# Water_Sensor.net
KiCad netlist of a schematic drawn in EAGLE
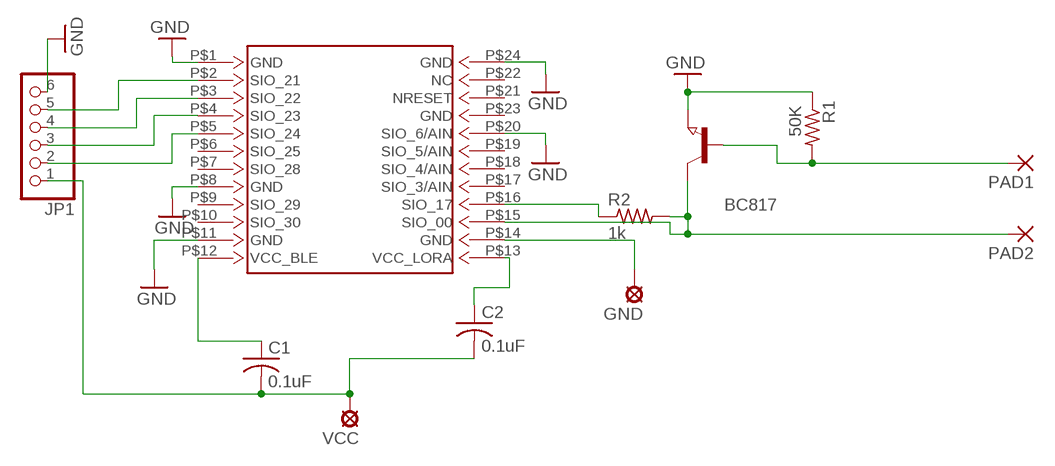
[diagram p0: schematic, sheet 1]

(export (version "E")
  (design (tool "Eeschema 10.0.6"))
  (components
    (comp (ref "BC817")
      (value "NPN-TRANSISTOR_SOT23")
      (footprint "eagle-import:SOT23")
      (libsource (lib "eagle-import") (part "NPN-TRANSISTOR_SOT23"))
    )
    (comp (ref "C1")
      (value "0.1uF")
      (footprint "eagle-import:C0805")
      (libsource (lib "eagle-import") (part "C-USC0805"))
    )
    (comp (ref "C2")
      (value "0.1uF")
      (footprint "eagle-import:C0805")
      (libsource (lib "eagle-import") (part "C-USC0805"))
    )
    (comp (ref "GND")
      (value "SE13")
      (footprint "eagle-import:SE13")
      (libsource (lib "eagle-import") (part "SE13"))
    )
    (comp (ref "JP1")
      (value "PINHD-1X6")
      (footprint "eagle-import:1X06")
      (libsource (lib "eagle-import") (part "PINHD-1X6"))
    )
    (comp (ref "PAD1")
      (value "SMD5")
      (footprint "eagle-import:SMD2,54-5,08")
      (libsource (lib "eagle-import") (part "SMD5"))
    )
    (comp (ref "PAD2")
      (value "SMD5")
      (footprint "eagle-import:SMD2,54-5,08")
      (libsource (lib "eagle-import") (part "SMD5"))
    )
    (comp (ref "R1")
      (value "50K")
      (footprint "eagle-import:M0805")
      (libsource (lib "eagle-import") (part "R-US_M0805"))
    )
    (comp (ref "R2")
      (value "1k")
      (footprint "eagle-import:M0805")
      (libsource (lib "eagle-import") (part "R-US_M0805"))
    )
    (comp (ref "RM191")
      (value "RM191RM1XX")
      (footprint "eagle-import:RM191")
      (libsource (lib "eagle-import") (part "RM191RM1XX"))
    )
    (comp (ref "VCC")
      (value "SE13")
      (footprint "eagle-import:SE13")
      (libsource (lib "eagle-import") (part "SE13"))
    )
  )
  (nets
    (net (code "1") (name "GND") (class "Default")
      (node (ref "BC817") (pin "2") (pinfunction "E_2") (pintype "passive"))
      (node (ref "GND") (pin "MP") (pinfunction "MP_MP") (pintype "passive"))
      (node (ref "JP1") (pin "6") (pinfunction "6_6") (pintype "passive"))
      (node (ref "R1") (pin "1") (pinfunction "1_1") (pintype "passive"))
      (node (ref "RM191") (pin "P$1") (pinfunction "GND_P$1") (pintype "bidirectional"))
      (node (ref "RM191") (pin "P$11") (pinfunction "GND_P$11") (pintype "bidirectional"))
      (node (ref "RM191") (pin "P$14") (pinfunction "GND_P$14") (pintype "bidirectional"))
      (node (ref "RM191") (pin "P$20") (pinfunction "SIO_6/AIN_P$20") (pintype "bidirectional"))
      (node (ref "RM191") (pin "P$24") (pinfunction "GND_P$24") (pintype "bidirectional"))
      (node (ref "RM191") (pin "P$8") (pinfunction "GND_P$8") (pintype "bidirectional"))
    )
    (net (code "2") (name "Net-(BC817-B)") (class "Default")
      (node (ref "BC817") (pin "1") (pinfunction "B_1") (pintype "passive"))
      (node (ref "PAD1") (pin "1") (pinfunction "P_1") (pintype "passive"))
      (node (ref "R1") (pin "2") (pinfunction "2_2") (pintype "passive"))
    )
    (net (code "3") (name "Net-(BC817-C)") (class "Default")
      (node (ref "BC817") (pin "3") (pinfunction "C_3") (pintype "passive"))
      (node (ref "PAD2") (pin "1") (pinfunction "P_1") (pintype "passive"))
      (node (ref "R2") (pin "2") (pinfunction "2_2") (pintype "passive"))
      (node (ref "RM191") (pin "P$15") (pinfunction "SIO_00_P$15") (pintype "bidirectional"))
    )
    (net (code "4") (name "Net-(C1-Pad2)") (class "Default")
      (node (ref "C1") (pin "2") (pinfunction "2_2") (pintype "passive"))
      (node (ref "C2") (pin "2") (pinfunction "2_2") (pintype "passive"))
      (node (ref "JP1") (pin "1") (pinfunction "1_1") (pintype "passive"))
      (node (ref "VCC") (pin "MP") (pinfunction "MP_MP") (pintype "passive"))
    )
    (net (code "5") (name "Net-(RM191-SIO_17)") (class "Default")
      (node (ref "R2") (pin "1") (pinfunction "1_1") (pintype "passive"))
      (node (ref "RM191") (pin "P$16") (pinfunction "SIO_17_P$16") (pintype "bidirectional"))
    )
    (net (code "6") (name "Net-(RM191-SIO_21)") (class "Default")
      (node (ref "JP1") (pin "5") (pinfunction "5_5") (pintype "passive"))
      (node (ref "RM191") (pin "P$2") (pinfunction "SIO_21_P$2") (pintype "bidirectional"))
    )
    (net (code "7") (name "Net-(RM191-SIO_22)") (class "Default")
      (node (ref "JP1") (pin "4") (pinfunction "4_4") (pintype "passive"))
      (node (ref "RM191") (pin "P$3") (pinfunction "SIO_22_P$3") (pintype "bidirectional"))
    )
    (net (code "8") (name "Net-(RM191-SIO_23)") (class "Default")
      (node (ref "JP1") (pin "3") (pinfunction "3_3") (pintype "passive"))
      (node (ref "RM191") (pin "P$4") (pinfunction "SIO_23_P$4") (pintype "bidirectional"))
    )
    (net (code "9") (name "Net-(RM191-SIO_24)") (class "Default")
      (node (ref "JP1") (pin "2") (pinfunction "2_2") (pintype "passive"))
      (node (ref "RM191") (pin "P$5") (pinfunction "SIO_24_P$5") (pintype "bidirectional"))
    )
    (net (code "10") (name "Net-(RM191-VCC_BLE)") (class "Default")
      (node (ref "C1") (pin "1") (pinfunction "1_1") (pintype "passive"))
      (node (ref "RM191") (pin "P$12") (pinfunction "VCC_BLE_P$12") (pintype "bidirectional"))
    )
    (net (code "11") (name "Net-(RM191-VCC_LORA)") (class "Default")
      (node (ref "C2") (pin "1") (pinfunction "1_1") (pintype "passive"))
      (node (ref "RM191") (pin "P$13") (pinfunction "VCC_LORA_P$13") (pintype "bidirectional"))
    )
    (net (code "12") (name "unconnected-(RM191-GND-PadP$23)") (class "Default")
      (node (ref "RM191") (pin "P$23") (pinfunction "GND_P$23") (pintype "bidirectional"))
    )
    (net (code "13") (name "unconnected-(RM191-NC-PadP$22)") (class "Default")
      (node (ref "RM191") (pin "P$22") (pinfunction "NC_P$22") (pintype "bidirectional"))
    )
    (net (code "14") (name "unconnected-(RM191-NRESET-PadP$21)") (class "Default")
      (node (ref "RM191") (pin "P$21") (pinfunction "NRESET_P$21") (pintype "bidirectional"))
    )
    (net (code "15") (name "unconnected-(RM191-SIO_3{slash}AIN-PadP$17)") (class "Default")
      (node (ref "RM191") (pin "P$17") (pinfunction "SIO_3/AIN_P$17") (pintype "bidirectional"))
    )
    (net (code "16") (name "unconnected-(RM191-SIO_4{slash}AIN-PadP$18)") (class "Default")
      (node (ref "RM191") (pin "P$18") (pinfunction "SIO_4/AIN_P$18") (pintype "bidirectional"))
    )
    (net (code "17") (name "unconnected-(RM191-SIO_5{slash}AIN-PadP$19)") (class "Default")
      (node (ref "RM191") (pin "P$19") (pinfunction "SIO_5/AIN_P$19") (pintype "bidirectional"))
    )
    (net (code "18") (name "unconnected-(RM191-SIO_25-PadP$6)") (class "Default")
      (node (ref "RM191") (pin "P$6") (pinfunction "SIO_25_P$6") (pintype "bidirectional"))
    )
    (net (code "19") (name "unconnected-(RM191-SIO_28-PadP$7)") (class "Default")
      (node (ref "RM191") (pin "P$7") (pinfunction "SIO_28_P$7") (pintype "bidirectional"))
    )
    (net (code "20") (name "unconnected-(RM191-SIO_29-PadP$9)") (class "Default")
      (node (ref "RM191") (pin "P$9") (pinfunction "SIO_29_P$9") (pintype "bidirectional"))
    )
    (net (code "21") (name "unconnected-(RM191-SIO_30-PadP$10)") (class "Default")
      (node (ref "RM191") (pin "P$10") (pinfunction "SIO_30_P$10") (pintype "bidirectional"))
    )
  )
)
